# v03.net
KiCad netlist of a schematic drawn in EAGLE
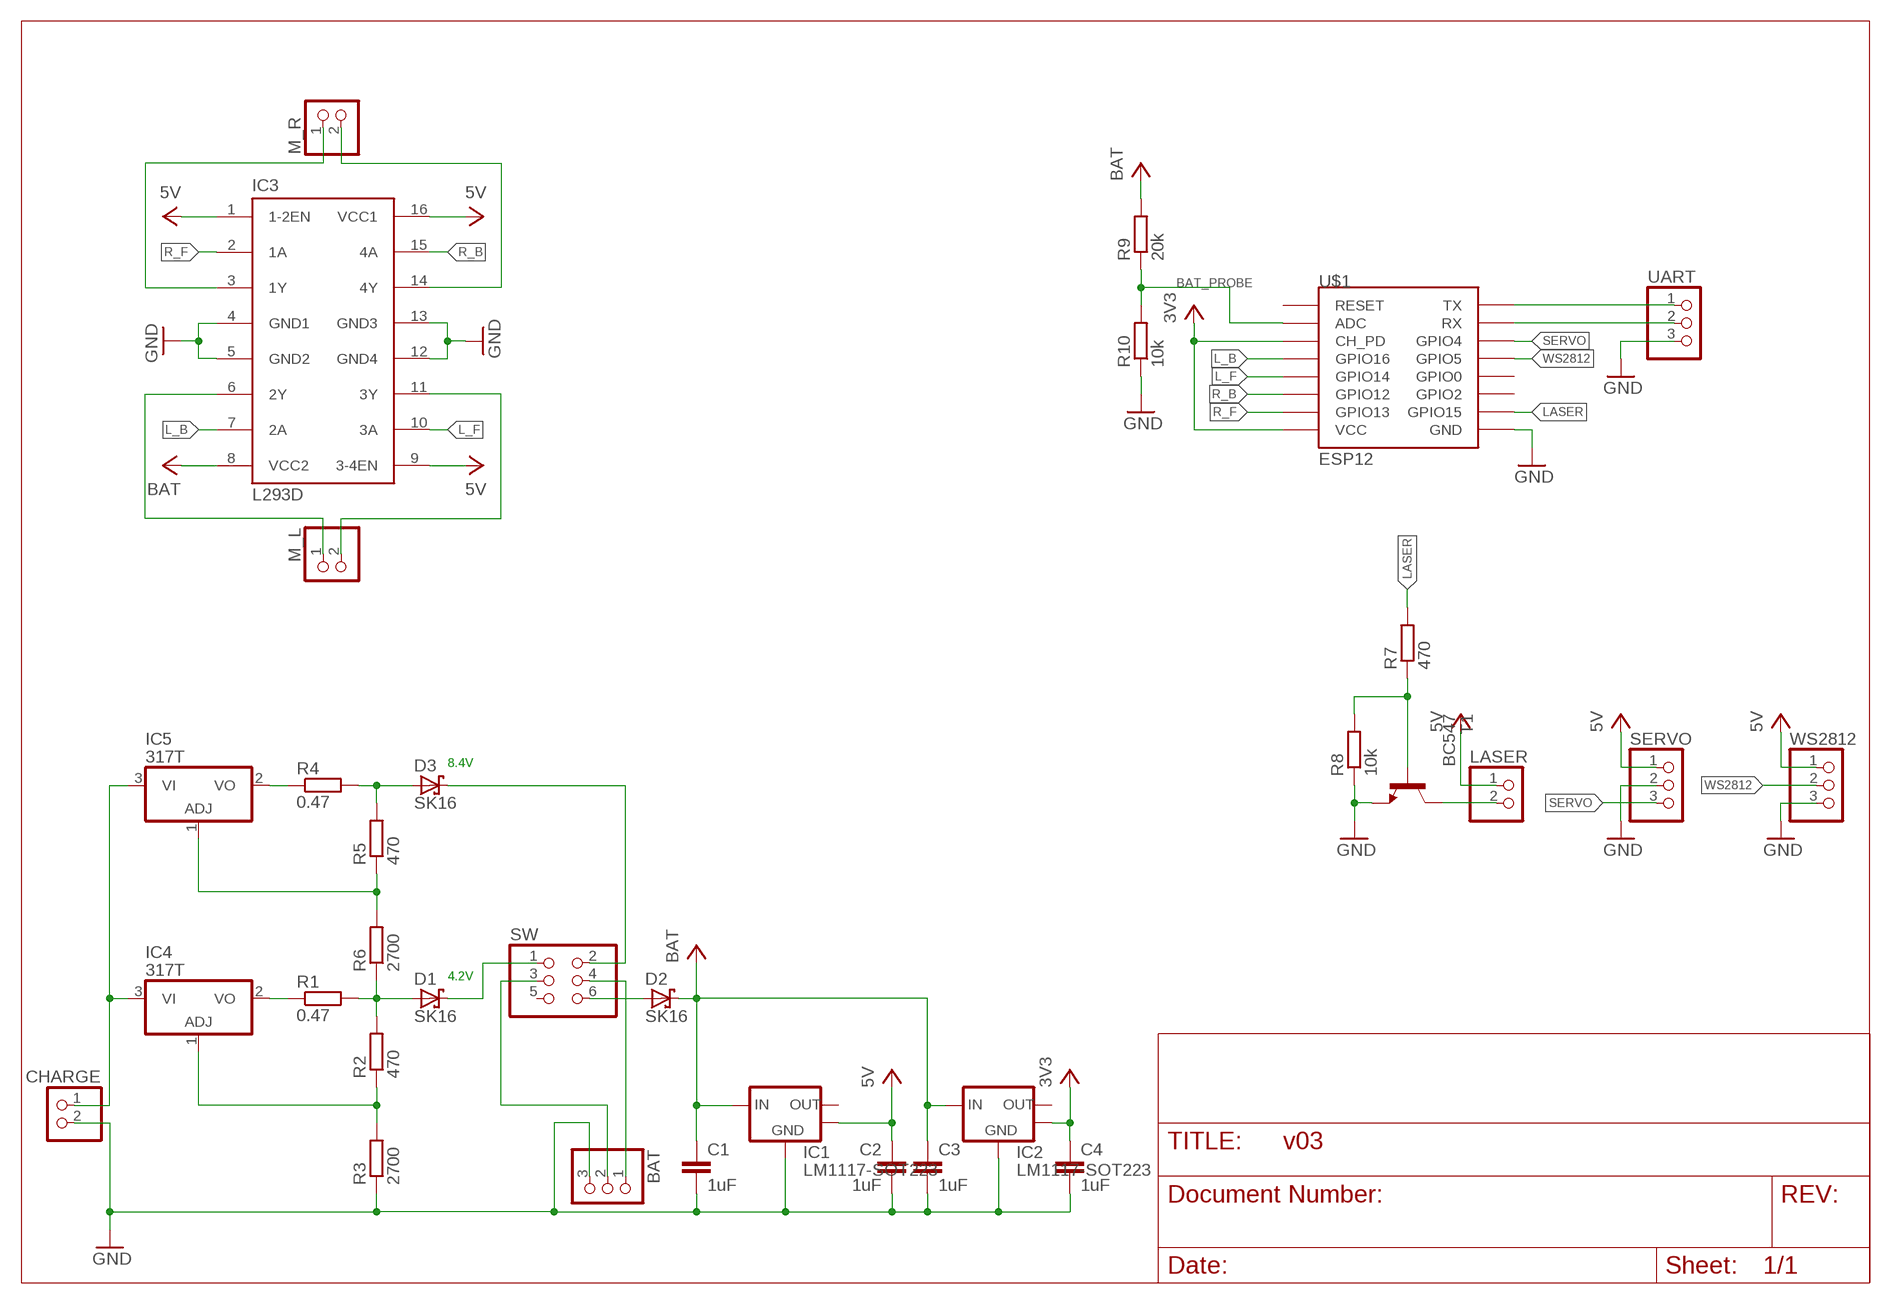
[diagram p0: schematic, sheet 1]

(export (version "E")
  (design (tool "Eeschema 10.0.6"))
  (components
    (comp (ref "BAT")
      (value "PINHD-1X3")
      (footprint "eagle-import:1X03")
      (libsource (lib "eagle-import") (part "PINHD-1X3"))
    )
    (comp (ref "C1")
      (value "1uF")
      (footprint "eagle-import:C0805")
      (libsource (lib "eagle-import") (part "C-EUC0805"))
    )
    (comp (ref "C2")
      (value "1uF")
      (footprint "eagle-import:C0805")
      (libsource (lib "eagle-import") (part "C-EUC0805"))
    )
    (comp (ref "C3")
      (value "1uF")
      (footprint "eagle-import:C0805")
      (libsource (lib "eagle-import") (part "C-EUC0805"))
    )
    (comp (ref "C4")
      (value "1uF")
      (footprint "eagle-import:C0805")
      (libsource (lib "eagle-import") (part "C-EUC0805"))
    )
    (comp (ref "CHARGE")
      (value "PINHD-1X2")
      (footprint "eagle-import:1X02")
      (libsource (lib "eagle-import") (part "PINHD-1X2"))
    )
    (comp (ref "D1")
      (value "SK16")
      (footprint "eagle-import:SMB")
      (libsource (lib "eagle-import") (part "SCHOTTKY-DIODESMD"))
    )
    (comp (ref "D2")
      (value "SK16")
      (footprint "eagle-import:SMB")
      (libsource (lib "eagle-import") (part "SCHOTTKY-DIODESMD"))
    )
    (comp (ref "D3")
      (value "SK16")
      (footprint "eagle-import:SMB")
      (libsource (lib "eagle-import") (part "SCHOTTKY-DIODESMD"))
    )
    (comp (ref "IC1")
      (value "LM1117-SOT223")
      (footprint "eagle-import:SOT-223-3")
      (libsource (lib "eagle-import") (part "LM1117-SOT223"))
    )
    (comp (ref "IC2")
      (value "LM1117-SOT223")
      (footprint "eagle-import:SOT-223-3")
      (libsource (lib "eagle-import") (part "LM1117-SOT223"))
    )
    (comp (ref "IC3")
      (value "L293D")
      (footprint "eagle-import:DIL16")
      (libsource (lib "eagle-import") (part "L293D"))
    )
    (comp (ref "IC4")
      (value "317T")
      (footprint "eagle-import:TO220H")
      (libsource (lib "eagle-import") (part "317T"))
    )
    (comp (ref "IC5")
      (value "317T")
      (footprint "eagle-import:TO220H")
      (libsource (lib "eagle-import") (part "317T"))
    )
    (comp (ref "LASER")
      (value "PINHD-1X2")
      (footprint "eagle-import:1X02")
      (libsource (lib "eagle-import") (part "PINHD-1X2"))
    )
    (comp (ref "M_L")
      (value "PINHD-1X2")
      (footprint "eagle-import:1X02")
      (libsource (lib "eagle-import") (part "PINHD-1X2"))
    )
    (comp (ref "M_R")
      (value "PINHD-1X2")
      (footprint "eagle-import:1X02")
      (libsource (lib "eagle-import") (part "PINHD-1X2"))
    )
    (comp (ref "R1")
      (value "0.47")
      (footprint "eagle-import:MINI_MELF-0207W")
      (libsource (lib "eagle-import") (part "resistor_R-EU_MELF0207W"))
    )
    (comp (ref "R2")
      (value "470")
      (footprint "eagle-import:R0805")
      (libsource (lib "eagle-import") (part "R-EU_R0805"))
    )
    (comp (ref "R3")
      (value "2700")
      (footprint "eagle-import:R0805")
      (libsource (lib "eagle-import") (part "R-EU_R0805"))
    )
    (comp (ref "R4")
      (value "0.47")
      (footprint "eagle-import:MINI_MELF-0207W")
      (libsource (lib "eagle-import") (part "resistor_R-EU_MELF0207W"))
    )
    (comp (ref "R5")
      (value "470")
      (footprint "eagle-import:R0805")
      (libsource (lib "eagle-import") (part "R-EU_R0805"))
    )
    (comp (ref "R6")
      (value "2700")
      (footprint "eagle-import:R0805")
      (libsource (lib "eagle-import") (part "R-EU_R0805"))
    )
    (comp (ref "R7")
      (value "470")
      (footprint "eagle-import:R0805")
      (libsource (lib "eagle-import") (part "R-EU_R0805"))
    )
    (comp (ref "R8")
      (value "10k")
      (footprint "eagle-import:R0805")
      (libsource (lib "eagle-import") (part "R-EU_R0805"))
    )
    (comp (ref "R9")
      (value "20k")
      (footprint "eagle-import:R0805")
      (libsource (lib "eagle-import") (part "R-EU_R0805"))
    )
    (comp (ref "R10")
      (value "10k")
      (footprint "eagle-import:R0805")
      (libsource (lib "eagle-import") (part "R-EU_R0805"))
    )
    (comp (ref "SERVO")
      (value "PINHD-1X3")
      (footprint "eagle-import:1X03")
      (libsource (lib "eagle-import") (part "PINHD-1X3"))
    )
    (comp (ref "SW")
      (value "PINHD-2X3")
      (footprint "eagle-import:2X03")
      (libsource (lib "eagle-import") (part "PINHD-2X3"))
    )
    (comp (ref "T1")
      (value "BC547")
      (footprint "eagle-import:TO92")
      (libsource (lib "eagle-import") (part "BC547"))
    )
    (comp (ref "U$1")
      (value "ESP12")
      (footprint "eagle-import:ESP12")
      (libsource (lib "eagle-import") (part "ESP12"))
    )
    (comp (ref "UART")
      (value "PINHD-1X3")
      (footprint "eagle-import:1X03")
      (libsource (lib "eagle-import") (part "PINHD-1X3"))
    )
    (comp (ref "WS2812")
      (value "PINHD-1X3")
      (footprint "eagle-import:1X03")
      (libsource (lib "eagle-import") (part "PINHD-1X3"))
    )
  )
  (nets
    (net (code "1") (name "/BAT_PROBE") (class "Default")
      (node (ref "R10") (pin "2") (pinfunction "2_2") (pintype "passive"))
      (node (ref "R9") (pin "1") (pinfunction "1_1") (pintype "passive"))
      (node (ref "U$1") (pin "ADC") (pinfunction "ADC_ADC") (pintype "bidirectional"))
    )
    (net (code "2") (name "3V3") (class "Default")
      (node (ref "C4") (pin "1") (pinfunction "1_1") (pintype "passive"))
      (node (ref "IC2") (pin "4") (pinfunction "HEATSINK_4") (pintype "bidirectional"))
      (node (ref "U$1") (pin "CH_PD") (pinfunction "CH_PD_CH_PD") (pintype "bidirectional"))
      (node (ref "U$1") (pin "VCC") (pinfunction "VCC_VCC") (pintype "bidirectional"))
    )
    (net (code "3") (name "5V") (class "Default")
      (node (ref "C2") (pin "1") (pinfunction "1_1") (pintype "passive"))
      (node (ref "IC1") (pin "4") (pinfunction "HEATSINK_4") (pintype "bidirectional"))
      (node (ref "IC3") (pin "1") (pinfunction "1-2EN_1") (pintype "input"))
      (node (ref "IC3") (pin "16") (pinfunction "VCC1_16") (pintype "power_in"))
      (node (ref "IC3") (pin "9") (pinfunction "3-4EN_9") (pintype "input"))
      (node (ref "LASER") (pin "1") (pinfunction "1_1") (pintype "passive"))
      (node (ref "SERVO") (pin "1") (pinfunction "1_1") (pintype "passive"))
      (node (ref "WS2812") (pin "1") (pinfunction "1_1") (pintype "passive"))
    )
    (net (code "4") (name "BAT") (class "Default")
      (node (ref "C1") (pin "1") (pinfunction "1_1") (pintype "passive"))
      (node (ref "C3") (pin "1") (pinfunction "1_1") (pintype "passive"))
      (node (ref "D2") (pin "C") (pinfunction "C_C") (pintype "passive"))
      (node (ref "IC1") (pin "3") (pinfunction "VIN_3") (pintype "bidirectional"))
      (node (ref "IC2") (pin "3") (pinfunction "VIN_3") (pintype "bidirectional"))
      (node (ref "IC3") (pin "8") (pinfunction "VCC2_8") (pintype "power_in"))
      (node (ref "R9") (pin "2") (pinfunction "2_2") (pintype "passive"))
    )
    (net (code "5") (name "GND") (class "Default")
      (node (ref "BAT") (pin "3") (pinfunction "3_3") (pintype "passive"))
      (node (ref "C1") (pin "2") (pinfunction "2_2") (pintype "passive"))
      (node (ref "C2") (pin "2") (pinfunction "2_2") (pintype "passive"))
      (node (ref "C3") (pin "2") (pinfunction "2_2") (pintype "passive"))
      (node (ref "C4") (pin "2") (pinfunction "2_2") (pintype "passive"))
      (node (ref "CHARGE") (pin "2") (pinfunction "2_2") (pintype "passive"))
      (node (ref "IC1") (pin "1") (pinfunction "GND_1") (pintype "bidirectional"))
      (node (ref "IC2") (pin "1") (pinfunction "GND_1") (pintype "bidirectional"))
      (node (ref "IC3") (pin "12") (pinfunction "GND4_12") (pintype "power_in"))
      (node (ref "IC3") (pin "13") (pinfunction "GND3_13") (pintype "power_in"))
      (node (ref "IC3") (pin "4") (pinfunction "GND1_4") (pintype "power_in"))
      (node (ref "IC3") (pin "5") (pinfunction "GND2_5") (pintype "power_in"))
      (node (ref "R10") (pin "1") (pinfunction "1_1") (pintype "passive"))
      (node (ref "R3") (pin "1") (pinfunction "1_1") (pintype "passive"))
      (node (ref "R8") (pin "1") (pinfunction "1_1") (pintype "passive"))
      (node (ref "SERVO") (pin "2") (pinfunction "2_2") (pintype "passive"))
      (node (ref "T1") (pin "1") (pinfunction "E_1") (pintype "passive"))
      (node (ref "U$1") (pin "GND") (pinfunction "GND_GND") (pintype "bidirectional"))
      (node (ref "UART") (pin "3") (pinfunction "3_3") (pintype "passive"))
      (node (ref "WS2812") (pin "3") (pinfunction "3_3") (pintype "passive"))
    )
    (net (code "6") (name "LASER") (class "Default")
      (node (ref "R7") (pin "2") (pinfunction "2_2") (pintype "passive"))
      (node (ref "U$1") (pin "GPIO15") (pinfunction "GPIO15_GPIO15") (pintype "bidirectional"))
    )
    (net (code "7") (name "L_B") (class "Default")
      (node (ref "IC3") (pin "7") (pinfunction "2A_7") (pintype "input"))
      (node (ref "U$1") (pin "GPIO16") (pinfunction "GPIO16_GPIO16") (pintype "bidirectional"))
    )
    (net (code "8") (name "L_F") (class "Default")
      (node (ref "IC3") (pin "10") (pinfunction "3A_10") (pintype "input"))
      (node (ref "U$1") (pin "GPIO14") (pinfunction "GPIO14_GPIO14") (pintype "bidirectional"))
    )
    (net (code "9") (name "Net-(BAT-Pad1)") (class "Default")
      (node (ref "BAT") (pin "1") (pinfunction "1_1") (pintype "passive"))
      (node (ref "SW") (pin "4") (pinfunction "4_4") (pintype "passive"))
    )
    (net (code "10") (name "Net-(BAT-Pad2)") (class "Default")
      (node (ref "BAT") (pin "2") (pinfunction "2_2") (pintype "passive"))
      (node (ref "SW") (pin "3") (pinfunction "3_3") (pintype "passive"))
    )
    (net (code "11") (name "Net-(D1-PadA)") (class "Default")
      (node (ref "D1") (pin "A") (pinfunction "A_A") (pintype "passive"))
      (node (ref "R1") (pin "2") (pinfunction "2_2") (pintype "passive"))
      (node (ref "R2") (pin "2") (pinfunction "2_2") (pintype "passive"))
      (node (ref "R6") (pin "1") (pinfunction "1_1") (pintype "passive"))
    )
    (net (code "12") (name "Net-(D1-PadC)") (class "Default")
      (node (ref "D1") (pin "C") (pinfunction "C_C") (pintype "passive"))
      (node (ref "SW") (pin "1") (pinfunction "1_1") (pintype "passive"))
    )
    (net (code "13") (name "Net-(D2-PadA)") (class "Default")
      (node (ref "D2") (pin "A") (pinfunction "A_A") (pintype "passive"))
      (node (ref "SW") (pin "6") (pinfunction "6_6") (pintype "passive"))
    )
    (net (code "14") (name "Net-(D3-PadA)") (class "Default")
      (node (ref "D3") (pin "A") (pinfunction "A_A") (pintype "passive"))
      (node (ref "R4") (pin "2") (pinfunction "2_2") (pintype "passive"))
      (node (ref "R5") (pin "2") (pinfunction "2_2") (pintype "passive"))
    )
    (net (code "15") (name "Net-(D3-PadC)") (class "Default")
      (node (ref "D3") (pin "C") (pinfunction "C_C") (pintype "passive"))
      (node (ref "SW") (pin "2") (pinfunction "2_2") (pintype "passive"))
    )
    (net (code "16") (name "Net-(IC3-1Y)") (class "Default")
      (node (ref "IC3") (pin "3") (pinfunction "1Y_3") (pintype "output"))
      (node (ref "M_R") (pin "1") (pinfunction "1_1") (pintype "passive"))
    )
    (net (code "17") (name "Net-(IC3-2Y)") (class "Default")
      (node (ref "IC3") (pin "6") (pinfunction "2Y_6") (pintype "output"))
      (node (ref "M_L") (pin "1") (pinfunction "1_1") (pintype "passive"))
    )
    (net (code "18") (name "Net-(IC3-3Y)") (class "Default")
      (node (ref "IC3") (pin "11") (pinfunction "3Y_11") (pintype "output"))
      (node (ref "M_L") (pin "2") (pinfunction "2_2") (pintype "passive"))
    )
    (net (code "19") (name "Net-(IC3-4Y)") (class "Default")
      (node (ref "IC3") (pin "14") (pinfunction "4Y_14") (pintype "output"))
      (node (ref "M_R") (pin "2") (pinfunction "2_2") (pintype "passive"))
    )
    (net (code "20") (name "Net-(IC4-ADJ)") (class "Default")
      (node (ref "IC4") (pin "1") (pinfunction "ADJ_1") (pintype "input"))
      (node (ref "R2") (pin "1") (pinfunction "1_1") (pintype "passive"))
      (node (ref "R3") (pin "2") (pinfunction "2_2") (pintype "passive"))
    )
    (net (code "21") (name "Net-(IC4-VI)") (class "Default")
      (node (ref "CHARGE") (pin "1") (pinfunction "1_1") (pintype "passive"))
      (node (ref "IC4") (pin "3") (pinfunction "VI_3") (pintype "input"))
      (node (ref "IC5") (pin "3") (pinfunction "VI_3") (pintype "input"))
    )
    (net (code "22") (name "Net-(IC4-VO)") (class "Default")
      (node (ref "IC4") (pin "2") (pinfunction "VO_2") (pintype "passive"))
      (node (ref "R1") (pin "1") (pinfunction "1_1") (pintype "passive"))
    )
    (net (code "23") (name "Net-(IC5-ADJ)") (class "Default")
      (node (ref "IC5") (pin "1") (pinfunction "ADJ_1") (pintype "input"))
      (node (ref "R5") (pin "1") (pinfunction "1_1") (pintype "passive"))
      (node (ref "R6") (pin "2") (pinfunction "2_2") (pintype "passive"))
    )
    (net (code "24") (name "Net-(IC5-VO)") (class "Default")
      (node (ref "IC5") (pin "2") (pinfunction "VO_2") (pintype "passive"))
      (node (ref "R4") (pin "1") (pinfunction "1_1") (pintype "passive"))
    )
    (net (code "25") (name "Net-(T1-B)") (class "Default")
      (node (ref "R7") (pin "1") (pinfunction "1_1") (pintype "passive"))
      (node (ref "R8") (pin "2") (pinfunction "2_2") (pintype "passive"))
      (node (ref "T1") (pin "2") (pinfunction "B_2") (pintype "passive"))
    )
    (net (code "26") (name "Net-(T1-C)") (class "Default")
      (node (ref "LASER") (pin "2") (pinfunction "2_2") (pintype "passive"))
      (node (ref "T1") (pin "3") (pinfunction "C_3") (pintype "passive"))
    )
    (net (code "27") (name "Net-(U$1-PadRX)") (class "Default")
      (node (ref "U$1") (pin "RX") (pinfunction "RX_RX") (pintype "bidirectional"))
      (node (ref "UART") (pin "2") (pinfunction "2_2") (pintype "passive"))
    )
    (net (code "28") (name "Net-(U$1-PadTX)") (class "Default")
      (node (ref "U$1") (pin "TX") (pinfunction "TX_TX") (pintype "bidirectional"))
      (node (ref "UART") (pin "1") (pinfunction "1_1") (pintype "passive"))
    )
    (net (code "29") (name "R_B") (class "Default")
      (node (ref "IC3") (pin "15") (pinfunction "4A_15") (pintype "input"))
      (node (ref "U$1") (pin "GPIO12") (pinfunction "GPIO12_GPIO12") (pintype "bidirectional"))
    )
    (net (code "30") (name "R_F") (class "Default")
      (node (ref "IC3") (pin "2") (pinfunction "1A_2") (pintype "input"))
      (node (ref "U$1") (pin "GPIO13") (pinfunction "GPIO13_GPIO13") (pintype "bidirectional"))
    )
    (net (code "31") (name "SERVO") (class "Default")
      (node (ref "SERVO") (pin "3") (pinfunction "3_3") (pintype "passive"))
      (node (ref "U$1") (pin "GPIO4") (pinfunction "GPIO4_GPIO4") (pintype "bidirectional"))
    )
    (net (code "32") (name "WS2812") (class "Default")
      (node (ref "U$1") (pin "GPIO5") (pinfunction "GPIO5_GPIO5") (pintype "bidirectional"))
      (node (ref "WS2812") (pin "2") (pinfunction "2_2") (pintype "passive"))
    )
    (net (code "33") (name "unconnected-(IC1-VOUT-Pad2)") (class "Default")
      (node (ref "IC1") (pin "2") (pinfunction "VOUT_2") (pintype "bidirectional"))
    )
    (net (code "34") (name "unconnected-(IC2-VOUT-Pad2)") (class "Default")
      (node (ref "IC2") (pin "2") (pinfunction "VOUT_2") (pintype "bidirectional"))
    )
    (net (code "35") (name "unconnected-(SW-Pad5)") (class "Default")
      (node (ref "SW") (pin "5") (pinfunction "5_5") (pintype "passive"))
    )
    (net (code "36") (name "unconnected-(U$1-PadGPIO0)") (class "Default")
      (node (ref "U$1") (pin "GPIO0") (pinfunction "GPIO0_GPIO0") (pintype "bidirectional"))
    )
    (net (code "37") (name "unconnected-(U$1-PadGPIO2)") (class "Default")
      (node (ref "U$1") (pin "GPIO2") (pinfunction "GPIO2_GPIO2") (pintype "bidirectional"))
    )
    (net (code "38") (name "unconnected-(U$1-PadRESET)") (class "Default")
      (node (ref "U$1") (pin "RESET") (pinfunction "RESET_RESET") (pintype "bidirectional"))
    )
  )
)
